# Sheet1.net
KiCad netlist of a schematic drawn in Altium Designer
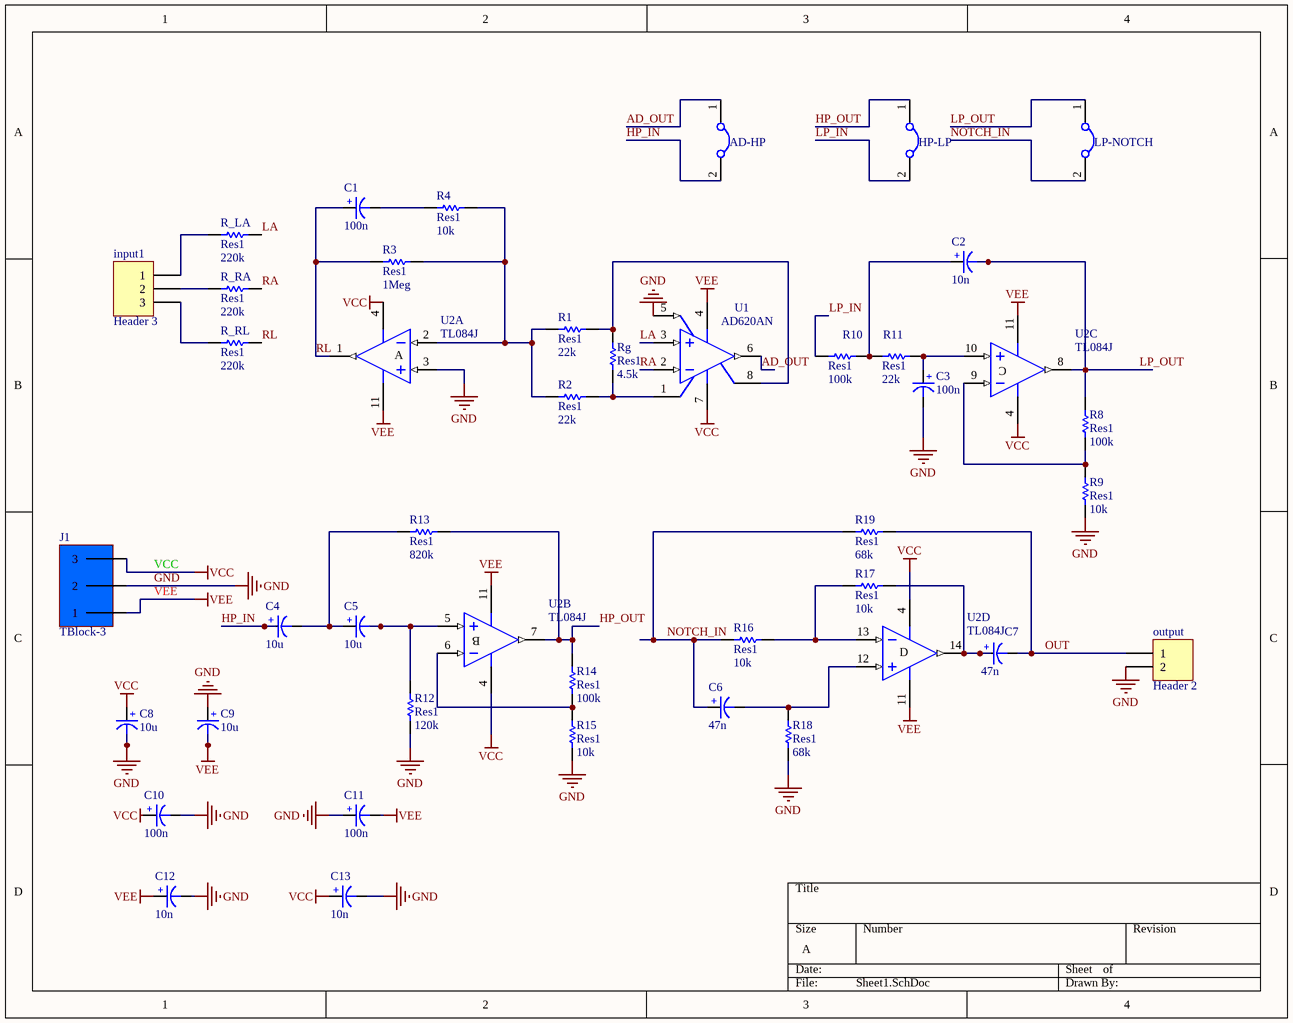
[diagram p0: Sheet1.SchDoc]

(export (version "E")
  (design (tool "Eeschema 10.0.6"))
  (components
    (comp (ref "AD-HP")
      (value "Jumper")
      (footprint "Header 2X1")
      (libsource (lib "AltiumLib1") (part "Jumper"))
    )
    (comp (ref "C1")
      (value "100n")
      (footprint "ELEC-CAP-RAD10-20")
      (description "Electrolytic Capacitor")
      (libsource (lib "AltiumLib1") (part "Capacitor Electrolytic"))
    )
    (comp (ref "C2")
      (value "10n")
      (footprint "ELEC-CAP-RAD10-20")
      (description "Electrolytic Capacitor")
      (libsource (lib "AltiumLib1") (part "Capacitor Electrolytic"))
    )
    (comp (ref "C3")
      (value "100n")
      (footprint "ELEC-CAP-RAD10-20")
      (description "Electrolytic Capacitor")
      (libsource (lib "AltiumLib1") (part "Capacitor Electrolytic"))
    )
    (comp (ref "C4")
      (value "10u")
      (footprint "ELEC-CAP-RAD10-20")
      (description "Electrolytic Capacitor")
      (libsource (lib "AltiumLib1") (part "Capacitor Electrolytic"))
    )
    (comp (ref "C5")
      (value "10u")
      (footprint "ELEC-CAP-RAD10-20")
      (description "Electrolytic Capacitor")
      (libsource (lib "AltiumLib1") (part "Capacitor Electrolytic"))
    )
    (comp (ref "C6")
      (value "47n")
      (footprint "ELEC-CAP-RAD10-20")
      (description "Electrolytic Capacitor")
      (libsource (lib "AltiumLib1") (part "Capacitor Electrolytic"))
    )
    (comp (ref "C7")
      (value "47n")
      (footprint "ELEC-CAP-RAD10-20")
      (description "Electrolytic Capacitor")
      (libsource (lib "AltiumLib1") (part "Capacitor Electrolytic"))
    )
    (comp (ref "C8")
      (value "10u")
      (footprint "ELEC-CAP-RAD10-20")
      (description "Electrolytic Capacitor")
      (libsource (lib "AltiumLib1") (part "Capacitor Electrolytic"))
    )
    (comp (ref "C9")
      (value "10u")
      (footprint "ELEC-CAP-RAD10-20")
      (description "Electrolytic Capacitor")
      (libsource (lib "AltiumLib1") (part "Capacitor Electrolytic"))
    )
    (comp (ref "C10")
      (value "100n")
      (footprint "ELEC-CAP-RAD10-20")
      (description "Electrolytic Capacitor")
      (libsource (lib "AltiumLib1") (part "Capacitor Electrolytic"))
    )
    (comp (ref "C11")
      (value "100n")
      (footprint "ELEC-CAP-RAD10-20")
      (description "Electrolytic Capacitor")
      (libsource (lib "AltiumLib1") (part "Capacitor Electrolytic"))
    )
    (comp (ref "C12")
      (value "10n")
      (footprint "ELEC-CAP-RAD10-20")
      (description "Electrolytic Capacitor")
      (libsource (lib "AltiumLib1") (part "Capacitor Electrolytic"))
    )
    (comp (ref "C13")
      (value "10n")
      (footprint "ELEC-CAP-RAD10-20")
      (description "Electrolytic Capacitor")
      (libsource (lib "AltiumLib1") (part "Capacitor Electrolytic"))
    )
    (comp (ref "HP-LP")
      (value "Jumper")
      (footprint "Header 2X1")
      (libsource (lib "AltiumLib1") (part "Jumper"))
    )
    (comp (ref "input1")
      (value "Header 3")
      (footprint "HDR1X3")
      (description "Header, 3-Pin")
      (fields (field (name "PUBLISHER") "Altium Limited"))
      (libsource (lib "Miscellaneous Connectors") (part "Header 3"))
    )
    (comp (ref "J1")
      (value "TBlock-3")
      (footprint "KF300-3 PIN")
      (libsource (lib "AltiumLib1") (part "TBlock-3"))
    )
    (comp (ref "LP-NOTCH")
      (value "Jumper")
      (footprint "Header 2X1")
      (libsource (lib "AltiumLib1") (part "Jumper"))
    )
    (comp (ref "output")
      (value "Header 2")
      (footprint "HDR1X2")
      (description "Header, 2-Pin")
      (fields (field (name "PUBLISHER") "Altium Limited"))
      (libsource (lib "Miscellaneous Connectors") (part "Header 2"))
    )
    (comp (ref "R1")
      (value "Res1")
      (footprint "AXIAL-0.3")
      (description "Resistor")
      (fields (field (name "ALTIUM_VALUE") "22k") (field (name "PUBLISHER") "Altium Limited"))
      (libsource (lib "Miscellaneous Devices") (part "Res1"))
    )
    (comp (ref "R2")
      (value "Res1")
      (footprint "AXIAL-0.3")
      (description "Resistor")
      (fields (field (name "ALTIUM_VALUE") "22k") (field (name "PUBLISHER") "Altium Limited"))
      (libsource (lib "Miscellaneous Devices") (part "Res1"))
    )
    (comp (ref "R3")
      (value "Res1")
      (footprint "AXIAL-0.3")
      (description "Resistor")
      (fields (field (name "ALTIUM_VALUE") "1Meg") (field (name "PUBLISHER") "Altium Limited"))
      (libsource (lib "Miscellaneous Devices") (part "Res1"))
    )
    (comp (ref "R4")
      (value "Res1")
      (footprint "AXIAL-0.3")
      (description "Resistor")
      (fields (field (name "ALTIUM_VALUE") "10k") (field (name "PUBLISHER") "Altium Limited"))
      (libsource (lib "Miscellaneous Devices") (part "Res1"))
    )
    (comp (ref "R8")
      (value "Res1")
      (footprint "AXIAL-0.3")
      (description "Resistor")
      (fields (field (name "ALTIUM_VALUE") "100k") (field (name "PUBLISHER") "Altium Limited"))
      (libsource (lib "Miscellaneous Devices") (part "Res1"))
    )
    (comp (ref "R9")
      (value "Res1")
      (footprint "AXIAL-0.3")
      (description "Resistor")
      (fields (field (name "ALTIUM_VALUE") "10k") (field (name "PUBLISHER") "Altium Limited"))
      (libsource (lib "Miscellaneous Devices") (part "Res1"))
    )
    (comp (ref "R10")
      (value "Res1")
      (footprint "AXIAL-0.3")
      (description "Resistor")
      (fields (field (name "ALTIUM_VALUE") "100k") (field (name "PUBLISHER") "Altium Limited"))
      (libsource (lib "Miscellaneous Devices") (part "Res1"))
    )
    (comp (ref "R11")
      (value "Res1")
      (footprint "AXIAL-0.3")
      (description "Resistor")
      (fields (field (name "ALTIUM_VALUE") "22k") (field (name "PUBLISHER") "Altium Limited"))
      (libsource (lib "Miscellaneous Devices") (part "Res1"))
    )
    (comp (ref "R12")
      (value "Res1")
      (footprint "AXIAL-0.3")
      (description "Resistor")
      (fields (field (name "ALTIUM_VALUE") "120k") (field (name "PUBLISHER") "Altium Limited"))
      (libsource (lib "Miscellaneous Devices") (part "Res1"))
    )
    (comp (ref "R13")
      (value "Res1")
      (footprint "AXIAL-0.3")
      (description "Resistor")
      (fields (field (name "ALTIUM_VALUE") "820k") (field (name "PUBLISHER") "Altium Limited"))
      (libsource (lib "Miscellaneous Devices") (part "Res1"))
    )
    (comp (ref "R14")
      (value "Res1")
      (footprint "AXIAL-0.3")
      (description "Resistor")
      (fields (field (name "ALTIUM_VALUE") "100k") (field (name "PUBLISHER") "Altium Limited"))
      (libsource (lib "Miscellaneous Devices") (part "Res1"))
    )
    (comp (ref "R15")
      (value "Res1")
      (footprint "AXIAL-0.3")
      (description "Resistor")
      (fields (field (name "ALTIUM_VALUE") "10k") (field (name "PUBLISHER") "Altium Limited"))
      (libsource (lib "Miscellaneous Devices") (part "Res1"))
    )
    (comp (ref "R16")
      (value "Res1")
      (footprint "AXIAL-0.3")
      (description "Resistor")
      (fields (field (name "ALTIUM_VALUE") "10k") (field (name "PUBLISHER") "Altium Limited"))
      (libsource (lib "Miscellaneous Devices") (part "Res1"))
    )
    (comp (ref "R17")
      (value "Res1")
      (footprint "AXIAL-0.3")
      (description "Resistor")
      (fields (field (name "ALTIUM_VALUE") "10k") (field (name "PUBLISHER") "Altium Limited"))
      (libsource (lib "Miscellaneous Devices") (part "Res1"))
    )
    (comp (ref "R18")
      (value "Res1")
      (footprint "AXIAL-0.3")
      (description "Resistor")
      (fields (field (name "ALTIUM_VALUE") "68k") (field (name "PUBLISHER") "Altium Limited"))
      (libsource (lib "Miscellaneous Devices") (part "Res1"))
    )
    (comp (ref "R19")
      (value "Res1")
      (footprint "AXIAL-0.3")
      (description "Resistor")
      (fields (field (name "ALTIUM_VALUE") "68k") (field (name "PUBLISHER") "Altium Limited"))
      (libsource (lib "Miscellaneous Devices") (part "Res1"))
    )
    (comp (ref "Rg")
      (value "Res1")
      (footprint "AXIAL-0.3")
      (description "Resistor")
      (fields (field (name "ALTIUM_VALUE") "4.5k") (field (name "PUBLISHER") "Altium Limited"))
      (libsource (lib "Miscellaneous Devices") (part "Res1"))
    )
    (comp (ref "R_LA")
      (value "Res1")
      (footprint "AXIAL-0.3")
      (description "Resistor")
      (fields (field (name "ALTIUM_VALUE") "220k") (field (name "PUBLISHER") "Altium Limited"))
      (libsource (lib "Miscellaneous Devices") (part "Res1"))
    )
    (comp (ref "R_RA")
      (value "Res1")
      (footprint "AXIAL-0.3")
      (description "Resistor")
      (fields (field (name "ALTIUM_VALUE") "220k") (field (name "PUBLISHER") "Altium Limited"))
      (libsource (lib "Miscellaneous Devices") (part "Res1"))
    )
    (comp (ref "R_RL")
      (value "Res1")
      (footprint "AXIAL-0.3")
      (description "Resistor")
      (fields (field (name "ALTIUM_VALUE") "220k") (field (name "PUBLISHER") "Altium Limited"))
      (libsource (lib "Miscellaneous Devices") (part "Res1"))
    )
    (comp (ref "U1")
      (value "AD620AN")
      (footprint "N-8")
      (description "Low-Cost, Low-Power Instrumentation Amplifier")
      (fields (field (name "PUBLISHER") "Altium Limited"))
      (libsource (lib "AD Instrumentation Amplifier") (part "AD620AN"))
    )
    (comp (ref "U2")
      (value "TL084J")
      (footprint "J014")
      (description "JFET-Input Operational Amplifier")
      (fields (field (name "PUBLISHER") "Altium Limited"))
      (libsource (lib "TI Operational Amplifier") (part "TL084J"))
    )
  )
  (nets
    (net (code "1") (name "/AD_OUT") (class "Default")
      (node (ref "AD-HP") (pin "1") (pinfunction "1_1") (pintype "passive"))
      (node (ref "U1") (pin "6") (pinfunction "OUT_6") (pintype "output"))
    )
    (net (code "2") (name "/HP_IN") (class "Default")
      (node (ref "AD-HP") (pin "2") (pinfunction "2_2") (pintype "passive"))
      (node (ref "C4") (pin "2") (pinfunction "+_2") (pintype "passive"))
    )
    (net (code "3") (name "/HP_OUT") (class "Default")
      (node (ref "HP-LP") (pin "1") (pinfunction "1_1") (pintype "passive"))
      (node (ref "R13") (pin "2") (pinfunction "2_2") (pintype "passive"))
      (node (ref "R14") (pin "2") (pinfunction "2_2") (pintype "passive"))
      (node (ref "U2") (pin "7") (pinfunction "OUT_7") (pintype "output"))
    )
    (net (code "4") (name "/LA") (class "Default")
      (node (ref "R_LA") (pin "1") (pinfunction "1_1") (pintype "passive"))
      (node (ref "U1") (pin "3") (pinfunction "+IN_3") (pintype "input"))
    )
    (net (code "5") (name "/LP_IN") (class "Default")
      (node (ref "HP-LP") (pin "2") (pinfunction "2_2") (pintype "passive"))
      (node (ref "R10") (pin "2") (pinfunction "2_2") (pintype "passive"))
    )
    (net (code "6") (name "/LP_OUT") (class "Default")
      (node (ref "C2") (pin "1") (pinfunction "-_1") (pintype "passive"))
      (node (ref "LP-NOTCH") (pin "1") (pinfunction "1_1") (pintype "passive"))
      (node (ref "R8") (pin "2") (pinfunction "2_2") (pintype "passive"))
      (node (ref "U2") (pin "8") (pinfunction "OUT_8") (pintype "output"))
    )
    (net (code "7") (name "/NOTCH_IN") (class "Default")
      (node (ref "C6") (pin "2") (pinfunction "+_2") (pintype "passive"))
      (node (ref "LP-NOTCH") (pin "2") (pinfunction "2_2") (pintype "passive"))
      (node (ref "R16") (pin "2") (pinfunction "2_2") (pintype "passive"))
      (node (ref "R19") (pin "2") (pinfunction "2_2") (pintype "passive"))
    )
    (net (code "8") (name "/OUT") (class "Default")
      (node (ref "C7") (pin "1") (pinfunction "-_1") (pintype "passive"))
      (node (ref "R19") (pin "1") (pinfunction "1_1") (pintype "passive"))
      (node (ref "output") (pin "1") (pinfunction "1_1") (pintype "passive"))
    )
    (net (code "9") (name "/RA") (class "Default")
      (node (ref "R_RA") (pin "2") (pinfunction "2_2") (pintype "passive"))
      (node (ref "U1") (pin "2") (pinfunction "-IN_2") (pintype "input"))
    )
    (net (code "10") (name "/RL") (class "Default")
      (node (ref "C1") (pin "2") (pinfunction "+_2") (pintype "passive"))
      (node (ref "R3") (pin "2") (pinfunction "2_2") (pintype "passive"))
      (node (ref "R_RL") (pin "2") (pinfunction "2_2") (pintype "passive"))
      (node (ref "U2") (pin "1") (pinfunction "OUT_1") (pintype "output"))
    )
    (net (code "11") (name "GND") (class "Default")
      (node (ref "C10") (pin "1") (pinfunction "-_1") (pintype "passive"))
      (node (ref "C11") (pin "2") (pinfunction "+_2") (pintype "passive"))
      (node (ref "C12") (pin "1") (pinfunction "-_1") (pintype "passive"))
      (node (ref "C13") (pin "1") (pinfunction "-_1") (pintype "passive"))
      (node (ref "C3") (pin "1") (pinfunction "-_1") (pintype "passive"))
      (node (ref "C8") (pin "1") (pinfunction "-_1") (pintype "passive"))
      (node (ref "C9") (pin "2") (pinfunction "+_2") (pintype "passive"))
      (node (ref "J1") (pin "2") (pinfunction "2_2") (pintype "passive"))
      (node (ref "R12") (pin "1") (pinfunction "1_1") (pintype "passive"))
      (node (ref "R15") (pin "1") (pinfunction "1_1") (pintype "passive"))
      (node (ref "R18") (pin "1") (pinfunction "1_1") (pintype "passive"))
      (node (ref "R9") (pin "1") (pinfunction "1_1") (pintype "passive"))
      (node (ref "U1") (pin "5") (pinfunction "REF_5") (pintype "input"))
      (node (ref "U2") (pin "3") (pinfunction "IN+_3") (pintype "input"))
      (node (ref "output") (pin "2") (pinfunction "2_2") (pintype "passive"))
    )
    (net (code "12") (name "Net-(C1--)") (class "Default")
      (node (ref "C1") (pin "1") (pinfunction "-_1") (pintype "passive"))
      (node (ref "R4") (pin "2") (pinfunction "2_2") (pintype "passive"))
    )
    (net (code "13") (name "Net-(C2-+)") (class "Default")
      (node (ref "C2") (pin "2") (pinfunction "+_2") (pintype "passive"))
      (node (ref "R10") (pin "1") (pinfunction "1_1") (pintype "passive"))
      (node (ref "R11") (pin "2") (pinfunction "2_2") (pintype "passive"))
    )
    (net (code "14") (name "Net-(C3-+)") (class "Default")
      (node (ref "C3") (pin "2") (pinfunction "+_2") (pintype "passive"))
      (node (ref "R11") (pin "1") (pinfunction "1_1") (pintype "passive"))
      (node (ref "U2") (pin "10") (pinfunction "IN+_10") (pintype "input"))
    )
    (net (code "15") (name "Net-(C4--)") (class "Default")
      (node (ref "C4") (pin "1") (pinfunction "-_1") (pintype "passive"))
      (node (ref "C5") (pin "2") (pinfunction "+_2") (pintype "passive"))
      (node (ref "R13") (pin "1") (pinfunction "1_1") (pintype "passive"))
    )
    (net (code "16") (name "Net-(C5--)") (class "Default")
      (node (ref "C5") (pin "1") (pinfunction "-_1") (pintype "passive"))
      (node (ref "R12") (pin "2") (pinfunction "2_2") (pintype "passive"))
      (node (ref "U2") (pin "5") (pinfunction "IN+_5") (pintype "input"))
    )
    (net (code "17") (name "Net-(C6--)") (class "Default")
      (node (ref "C6") (pin "1") (pinfunction "-_1") (pintype "passive"))
      (node (ref "R18") (pin "2") (pinfunction "2_2") (pintype "passive"))
      (node (ref "U2") (pin "12") (pinfunction "IN+_12") (pintype "input"))
    )
    (net (code "18") (name "Net-(C7-+)") (class "Default")
      (node (ref "C7") (pin "2") (pinfunction "+_2") (pintype "passive"))
      (node (ref "R17") (pin "1") (pinfunction "1_1") (pintype "passive"))
      (node (ref "U2") (pin "14") (pinfunction "OUT_14") (pintype "output"))
    )
    (net (code "19") (name "Net-(R1-Pad1)") (class "Default")
      (node (ref "R1") (pin "1") (pinfunction "1_1") (pintype "passive"))
      (node (ref "Rg") (pin "2") (pinfunction "2_2") (pintype "passive"))
      (node (ref "U1") (pin "8") (pinfunction "RG_8") (pintype "passive"))
    )
    (net (code "20") (name "Net-(R2-Pad1)") (class "Default")
      (node (ref "R2") (pin "1") (pinfunction "1_1") (pintype "passive"))
      (node (ref "Rg") (pin "1") (pinfunction "1_1") (pintype "passive"))
      (node (ref "U1") (pin "1") (pinfunction "RG_1") (pintype "passive"))
    )
    (net (code "21") (name "Net-(R_LA-Pad2)") (class "Default")
      (node (ref "R_LA") (pin "2") (pinfunction "2_2") (pintype "passive"))
      (node (ref "input1") (pin "1") (pinfunction "1_1") (pintype "passive"))
    )
    (net (code "22") (name "Net-(R_RA-Pad1)") (class "Default")
      (node (ref "R_RA") (pin "1") (pinfunction "1_1") (pintype "passive"))
      (node (ref "input1") (pin "2") (pinfunction "2_2") (pintype "passive"))
    )
    (net (code "23") (name "Net-(R_RL-Pad1)") (class "Default")
      (node (ref "R_RL") (pin "1") (pinfunction "1_1") (pintype "passive"))
      (node (ref "input1") (pin "3") (pinfunction "3_3") (pintype "passive"))
    )
    (net (code "24") (name "Net-(U2A-IN-)") (class "Default")
      (node (ref "R1") (pin "2") (pinfunction "2_2") (pintype "passive"))
      (node (ref "R2") (pin "2") (pinfunction "2_2") (pintype "passive"))
      (node (ref "R3") (pin "1") (pinfunction "1_1") (pintype "passive"))
      (node (ref "R4") (pin "1") (pinfunction "1_1") (pintype "passive"))
      (node (ref "U2") (pin "2") (pinfunction "IN-_2") (pintype "input"))
    )
    (net (code "25") (name "Net-(U2B-IN-)") (class "Default")
      (node (ref "R14") (pin "1") (pinfunction "1_1") (pintype "passive"))
      (node (ref "R15") (pin "2") (pinfunction "2_2") (pintype "passive"))
      (node (ref "U2") (pin "6") (pinfunction "IN-_6") (pintype "input"))
    )
    (net (code "26") (name "Net-(U2C-IN-)") (class "Default")
      (node (ref "R8") (pin "1") (pinfunction "1_1") (pintype "passive"))
      (node (ref "R9") (pin "2") (pinfunction "2_2") (pintype "passive"))
      (node (ref "U2") (pin "9") (pinfunction "IN-_9") (pintype "input"))
    )
    (net (code "27") (name "Net-(U2D-IN-)") (class "Default")
      (node (ref "R16") (pin "1") (pinfunction "1_1") (pintype "passive"))
      (node (ref "R17") (pin "2") (pinfunction "2_2") (pintype "passive"))
      (node (ref "U2") (pin "13") (pinfunction "IN-_13") (pintype "input"))
    )
    (net (code "28") (name "VCC") (class "Default")
      (node (ref "C13") (pin "2") (pinfunction "+_2") (pintype "passive"))
      (node (ref "C8") (pin "2") (pinfunction "+_2") (pintype "passive"))
      (node (ref "J1") (pin "3") (pinfunction "3_3") (pintype "passive"))
      (node (ref "U1") (pin "7") (pinfunction "V+_7") (pintype "power_in"))
      (node (ref "U2") (pin "4") (pinfunction "V+_4") (pintype "power_in"))
    )
    (net (code "29") (name "VEE") (class "Default")
      (node (ref "C11") (pin "1") (pinfunction "-_1") (pintype "passive"))
      (node (ref "C12") (pin "2") (pinfunction "+_2") (pintype "passive"))
      (node (ref "C9") (pin "1") (pinfunction "-_1") (pintype "passive"))
      (node (ref "J1") (pin "1") (pinfunction "1_1") (pintype "passive"))
      (node (ref "U1") (pin "4") (pinfunction "V-_4") (pintype "power_in"))
      (node (ref "U2") (pin "11") (pinfunction "V-_11") (pintype "power_in"))
    )
    (net (code "30") (name "unconnected-(C10-+-Pad2)") (class "Default")
      (node (ref "C10") (pin "2") (pinfunction "+_2") (pintype "passive"))
    )
  )
)
